# Sensing_-_Temperature.net
KiCad netlist of a schematic drawn in Altium Designer
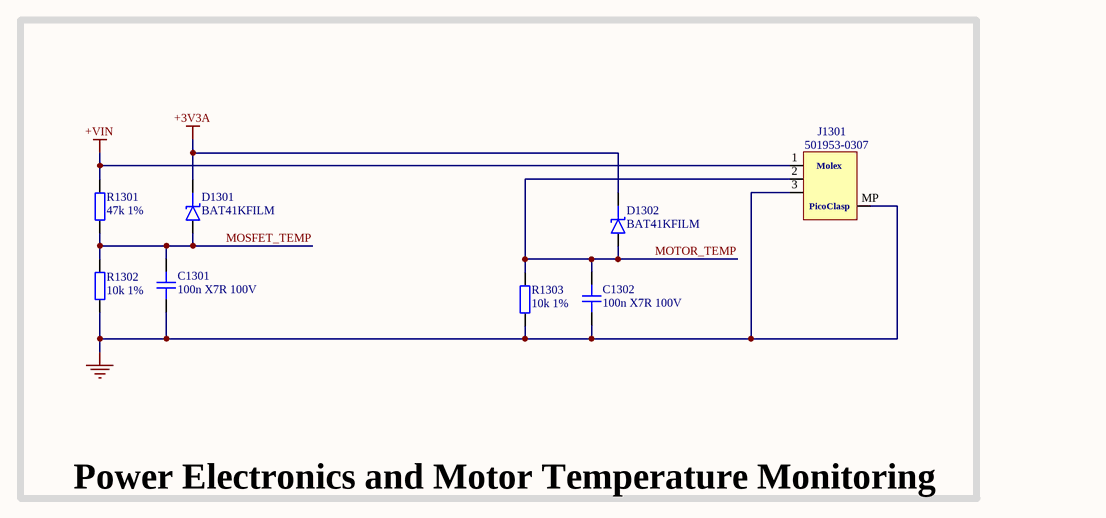
[diagram p0: Sensing - Temperature.SchDoc]

(export (version "E")
  (design (tool "Eeschema 10.0.6"))
  (components
    (comp (ref "C1301")
      (value "100n X7R 100V")
      (footprint "CAP_0603")
      (description "Capacitor SMD 0603")
      (fields
        (field (name "MANUFACTURER") "CCTC")
        (field (name "MANUFACTURER PART NUMBER") "TCC0603X7R104K101CT")
      )
      (libsource (lib "Schematic-Lib-PhilsLab") (part "CAP_0603"))
    )
    (comp (ref "C1302")
      (value "100n X7R 100V")
      (footprint "CAP_0603")
      (description "Capacitor SMD 0603")
      (fields
        (field (name "MANUFACTURER") "CCTC")
        (field (name "MANUFACTURER PART NUMBER") "TCC0603X7R104K101CT")
      )
      (libsource (lib "Schematic-Lib-PhilsLab") (part "CAP_0603"))
    )
    (comp (ref "D1301")
      (value "BAT41KFILM")
      (footprint "SOD-523")
      (description "Diode Schottky SMD SOD-323")
      (fields (field (name "MANUFACTURER") "STMicroelectronics"))
      (libsource (lib "Schematic-Lib-PhilsLab") (part "D_SCHOTTKY_SOD_523"))
    )
    (comp (ref "D1302")
      (value "BAT41KFILM")
      (footprint "SOD-523")
      (description "Diode Schottky SMD SOD-323")
      (fields (field (name "MANUFACTURER") "STMicroelectronics"))
      (libsource (lib "Schematic-Lib-PhilsLab") (part "D_SCHOTTKY_SOD_523"))
    )
    (comp (ref "J1301")
      (value "501953-0307")
      (footprint "5019530307")
      (description "Headers & Wire Housings 1.0WtBWaferAssyR/A1- -Row3Ckt+LKEmbsTpPkg")
      (libsource (lib "Schematic-Lib-PhilsLab") (part "501953-0307"))
    )
    (comp (ref "R1301")
      (value "47k 1%")
      (footprint "RES_0603")
      (description "Resistor SMD 0603")
      (fields
        (field (name "MANUFACTURER") "Vishay Intertech")
        (field (name "MANUFACTURER PART NUMBER") "NTCS0603E3473FHT")
      )
      (libsource (lib "Schematic-Lib-PhilsLab") (part "RES_0603"))
    )
    (comp (ref "R1302")
      (value "10k 1%")
      (footprint "RES_0603")
      (description "Resistor SMD 0603")
      (fields
        (field (name "MANUFACTURER") "YAGEO")
        (field (name "MANUFACTURER PART NUMBER") "RC0603FR-07140KL")
      )
      (libsource (lib "Schematic-Lib-PhilsLab") (part "RES_0603"))
    )
    (comp (ref "R1303")
      (value "10k 1%")
      (footprint "RES_0603")
      (description "Resistor SMD 0603")
      (fields
        (field (name "MANUFACTURER") "YAGEO")
        (field (name "MANUFACTURER PART NUMBER") "RC0603FR-07140KL")
      )
      (libsource (lib "Schematic-Lib-PhilsLab") (part "RES_0603"))
    )
  )
  (nets
    (net (code "1") (name "+3V3A") (class "Default")
      (node (ref "D1301") (pin "K") (pinfunction "K_K") (pintype "passive"))
      (node (ref "D1302") (pin "K") (pinfunction "K_K") (pintype "passive"))
    )
    (net (code "2") (name "+VIN") (class "Default")
      (node (ref "J1301") (pin "1") (pinfunction "1_1") (pintype "passive"))
      (node (ref "R1301") (pin "2") (pinfunction "2_2") (pintype "passive"))
    )
    (net (code "3") (name "/MOSFET_TEMP") (class "Default")
      (node (ref "C1301") (pin "2") (pinfunction "2_2") (pintype "passive"))
      (node (ref "D1301") (pin "A") (pinfunction "A_A") (pintype "passive"))
      (node (ref "R1301") (pin "1") (pinfunction "1_1") (pintype "passive"))
      (node (ref "R1302") (pin "2") (pinfunction "2_2") (pintype "passive"))
    )
    (net (code "4") (name "/MOTOR_TEMP") (class "Default")
      (node (ref "C1302") (pin "2") (pinfunction "2_2") (pintype "passive"))
      (node (ref "D1302") (pin "A") (pinfunction "A_A") (pintype "passive"))
      (node (ref "J1301") (pin "2") (pinfunction "2_2") (pintype "passive"))
      (node (ref "R1303") (pin "2") (pinfunction "2_2") (pintype "passive"))
    )
    (net (code "5") (name "GND") (class "Default")
      (node (ref "C1301") (pin "1") (pinfunction "1_1") (pintype "passive"))
      (node (ref "C1302") (pin "1") (pinfunction "1_1") (pintype "passive"))
      (node (ref "J1301") (pin "3") (pinfunction "3_3") (pintype "passive"))
      (node (ref "J1301") (pin "MP") (pinfunction "MP_MP") (pintype "passive"))
      (node (ref "R1302") (pin "1") (pinfunction "1_1") (pintype "passive"))
      (node (ref "R1303") (pin "1") (pinfunction "1_1") (pintype "passive"))
    )
  )
)
